# ESP32_MCU.net
KiCad netlist of a schematic drawn in Altium Designer
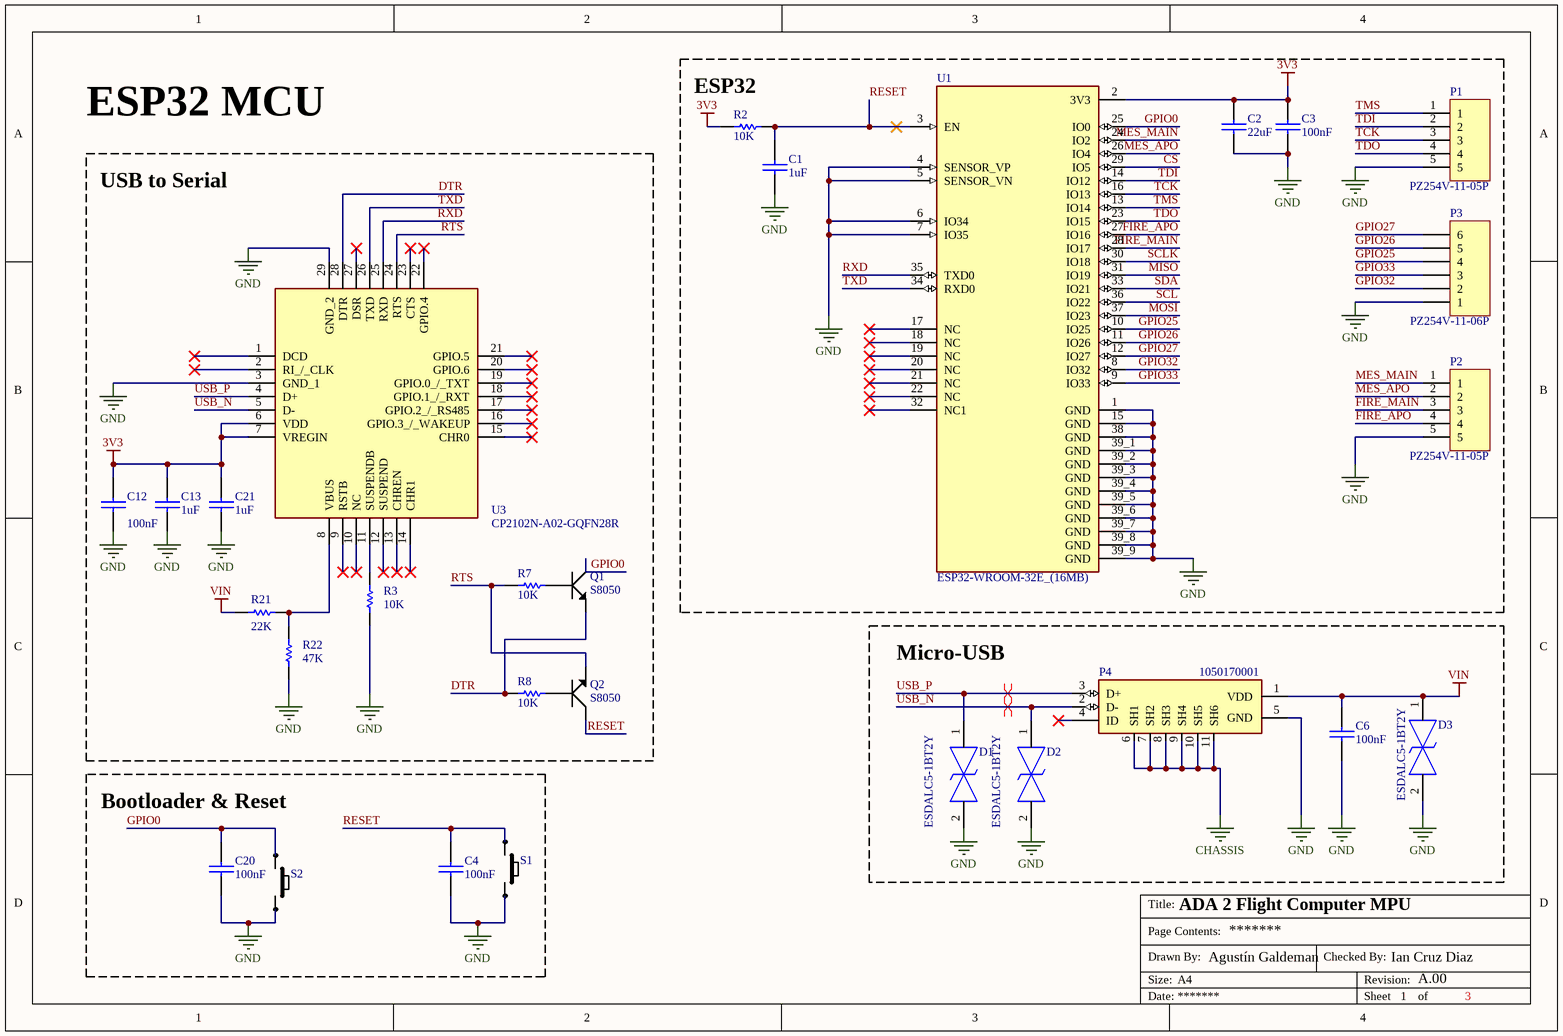
[diagram p0: ESP32 MCU.SchDoc]

(export (version "E")
  (design (tool "Eeschema 10.0.6"))
  (components
    (comp (ref "C1")
      (value "1uF")
      (footprint "CAPSMD0805")
      (description "Capacitor SMD 4.7nF")
      (fields
        (field (name "MANUFACTURER") "FH (Guangdong Fenghua Advanced Tech)")
        (field (name "MANUFACTURER PART NUMBER") "0805F105Z250NT")
      )
      (libsource (lib "ESP32 Platform") (part "CAP"))
    )
    (comp (ref "C2")
      (value "22uF")
      (footprint "CAPSMD0805")
      (description "Capacitor SMD 4.7nF")
      (fields
        (field (name "MANUFACTURER") "Samsung Electro-Mechanics")
        (field (name "MANUFACTURER PART NUMBER") "CL21A226KPCLRNC")
      )
      (libsource (lib "ESP32 Platform") (part "CAP"))
    )
    (comp (ref "C3")
      (value "100nF")
      (footprint "CAPSMD0805")
      (description "Capacitor SMD 4.7nF")
      (fields
        (field (name "MANUFACTURER") "FH (Guangdong Fenghua Advanced Tech)")
        (field (name "MANUFACTURER PART NUMBER") "0805B104M500NT")
      )
      (libsource (lib "ESP32 Platform") (part "CAP"))
    )
    (comp (ref "C4")
      (value "100nF")
      (footprint "CAPSMD0805")
      (description "Capacitor SMD 4.7nF")
      (fields
        (field (name "MANUFACTURER") "FH (Guangdong Fenghua Advanced Tech)")
        (field (name "MANUFACTURER PART NUMBER") "0805B104M500NT")
      )
      (libsource (lib "ESP32 Platform") (part "CAP"))
    )
    (comp (ref "C6")
      (value "100nF")
      (footprint "CAPSMD0805")
      (description "Capacitor SMD 4.7nF")
      (fields
        (field (name "MANUFACTURER") "FH (Guangdong Fenghua Advanced Tech)")
        (field (name "MANUFACTURER PART NUMBER") "0805B104M500NT")
      )
      (libsource (lib "ESP32 Platform") (part "CAP"))
    )
    (comp (ref "C12")
      (value "100nF")
      (footprint "CAPSMD0805")
      (description "Capacitor SMD 4.7nF")
      (fields
        (field (name "MANUFACTURER") "FH (Guangdong Fenghua Advanced Tech)")
        (field (name "MANUFACTURER PART NUMBER") "0805B104M500NT")
      )
      (libsource (lib "ESP32 Platform") (part "CAP"))
    )
    (comp (ref "C13")
      (value "1uF")
      (footprint "CAPSMD0805")
      (description "Capacitor SMD 4.7nF")
      (fields
        (field (name "MANUFACTURER") "FH (Guangdong Fenghua Advanced Tech)")
        (field (name "MANUFACTURER PART NUMBER") "0805F105Z250NT")
      )
      (libsource (lib "ESP32 Platform") (part "CAP"))
    )
    (comp (ref "C20")
      (value "100nF")
      (footprint "CAPSMD0805")
      (description "Capacitor SMD 4.7nF")
      (fields
        (field (name "MANUFACTURER") "FH (Guangdong Fenghua Advanced Tech)")
        (field (name "MANUFACTURER PART NUMBER") "0805B104M500NT")
      )
      (libsource (lib "ESP32 Platform") (part "CAP"))
    )
    (comp (ref "C21")
      (value "1uF")
      (footprint "CAPSMD0805")
      (description "Capacitor SMD 4.7nF")
      (fields
        (field (name "MANUFACTURER") "FH (Guangdong Fenghua Advanced Tech)")
        (field (name "MANUFACTURER PART NUMBER") "0805F105Z250NT")
      )
      (libsource (lib "ESP32 Platform") (part "CAP"))
    )
    (comp (ref "D1")
      (value "~")
      (footprint "ESDALC51BT2")
      (description "ESD Suppressors / TVS Diodes Single Line Transil Vbr 5V min 26pF 0")
      (fields
        (field (name "MANUFACTURER") "STMicroelectronics")
        (field (name "MANUFACTURER PART NUMBER") "ESDALC5-1BT2Y")
      )
      (libsource (lib "ESP32 Platform") (part "ESDALC5-1BT2"))
    )
    (comp (ref "D2")
      (value "~")
      (footprint "ESDALC51BT2")
      (description "ESD Suppressors / TVS Diodes Single Line Transil Vbr 5V min 26pF 0")
      (fields
        (field (name "MANUFACTURER") "STMicroelectronics")
        (field (name "MANUFACTURER PART NUMBER") "ESDALC5-1BT2Y")
      )
      (libsource (lib "ESP32 Platform") (part "ESDALC5-1BT2"))
    )
    (comp (ref "D3")
      (value "~")
      (footprint "ESDALC51BT2")
      (description "ESD Suppressors / TVS Diodes Single Line Transil Vbr 5V min 26pF 0")
      (fields
        (field (name "MANUFACTURER") "STMicroelectronics")
        (field (name "MANUFACTURER PART NUMBER") "ESDALC5-1BT2Y")
      )
      (libsource (lib "ESP32 Platform") (part "ESDALC5-1BT2"))
    )
    (comp (ref "P1")
      (value "HEADER-5P-SR")
      (footprint "PZ254V-11-05P")
      (fields (field (name "MANUFACTURER") "XFCN") (field (name "MANUFACTURER PART NUMBER") "PZ254V-11-05P"))
      (libsource (lib "ESP32 Platform") (part "HEADER-5P-SR"))
    )
    (comp (ref "P2")
      (value "HEADER-5P-SR")
      (footprint "PZ254V-11-05P")
      (fields (field (name "MANUFACTURER") "XFCN") (field (name "MANUFACTURER PART NUMBER") "PZ254V-11-05P"))
      (libsource (lib "ESP32 Platform") (part "HEADER-5P-SR"))
    )
    (comp (ref "P3")
      (value "~")
      (footprint "HDR1X6")
      (description "Header, 6-Pin")
      (fields (field (name "MANUFACTURER") "XFCN") (field (name "MANUFACTURER PART NUMBER") "PZ254V-11-06P"))
      (libsource (lib "Miscellaneous Connectors") (part "Header 6"))
    )
    (comp (ref "P4")
      (value "~")
      (footprint "Micro-B Molex 1051640001")
      (description "USB - micro B USB 2.0 Receptacle Connector 5 Position Surface Mount, Right Angle; Through Hole")
      (fields (field (name "MANUFACTURER") "MOLEX") (field (name "MANUFACTURER PART NUMBER") "1050170001"))
      (libsource (lib "ESP32 Platform") (part "Micro-B Molex 1051640001"))
    )
    (comp (ref "Q1")
      (value "S8050")
      (footprint "SOT-23-3")
      (description "25V 300mW 500mA SOT-23  Bipolar Transistors - BJT ROHS")
      (fields (field (name "MANUFACTURER") "JSMSEMI") (field (name "MANUFACTURER PART NUMBER") "S8050"))
      (libsource (lib "ESP32 Platform") (part "S8050"))
    )
    (comp (ref "Q2")
      (value "S8050")
      (footprint "SOT-23-3")
      (description "25V 300mW 500mA SOT-23  Bipolar Transistors - BJT ROHS")
      (fields (field (name "MANUFACTURER") "JSMSEMI") (field (name "MANUFACTURER PART NUMBER") "S8050"))
      (libsource (lib "ESP32 Platform") (part "S8050"))
    )
    (comp (ref "R2")
      (value "10K")
      (footprint "0805")
      (description "Resistencia SMD 470ohms")
      (fields
        (field (name "MANUFACTURER") "Viking Tech")
        (field (name "MANUFACTURER PART NUMBER") "ARG05BTC1002")
      )
      (libsource (lib "ESP32 Platform") (part "RES"))
    )
    (comp (ref "R3")
      (value "10K")
      (footprint "0805")
      (description "Resistencia SMD 470ohms")
      (fields
        (field (name "MANUFACTURER") "Viking Tech")
        (field (name "MANUFACTURER PART NUMBER") "ARG05BTC1002")
      )
      (libsource (lib "ESP32 Platform") (part "RES"))
    )
    (comp (ref "R7")
      (value "10K")
      (footprint "0805")
      (description "Resistencia SMD 470ohms")
      (fields
        (field (name "MANUFACTURER") "Viking Tech")
        (field (name "MANUFACTURER PART NUMBER") "ARG05BTC1002")
      )
      (libsource (lib "ESP32 Platform") (part "RES"))
    )
    (comp (ref "R8")
      (value "10K")
      (footprint "0805")
      (description "Resistencia SMD 470ohms")
      (fields
        (field (name "MANUFACTURER") "Viking Tech")
        (field (name "MANUFACTURER PART NUMBER") "ARG05BTC1002")
      )
      (libsource (lib "ESP32 Platform") (part "RES"))
    )
    (comp (ref "R21")
      (value "22K")
      (footprint "0805")
      (description "Resistencia SMD 470ohms")
      (fields
        (field (name "MANUFACTURER") "KOA Speer Elec")
        (field (name "MANUFACTURER PART NUMBER") "RN73H2ATTD2202B25")
      )
      (libsource (lib "ESP32 Platform") (part "RES"))
    )
    (comp (ref "R22")
      (value "47K")
      (footprint "0805")
      (description "Resistencia SMD 470ohms")
      (fields
        (field (name "MANUFACTURER") "Sunway")
        (field (name "MANUFACTURER PART NUMBER") "SC0805J4702F4ANRH")
      )
      (libsource (lib "ESP32 Platform") (part "RES"))
    )
    (comp (ref "S1")
      (value "RESET")
      (footprint "PUSHBUTTON_2")
      (description "SWITCH TACTILE SPST-NO 0.05A 12V")
      (fields
        (field (name "MANUFACTURER") "C&K")
        (field (name "MANUFACTURER PART NUMBER") "PTS645SM43SMTR92LFS")
      )
      (libsource (lib "Library") (part "PUSHBUTTON_2"))
    )
    (comp (ref "S2")
      (value "BOOT")
      (footprint "PUSHBUTTON_2")
      (description "SWITCH TACTILE SPST-NO 0.05A 12V")
      (fields
        (field (name "MANUFACTURER") "C&K")
        (field (name "MANUFACTURER PART NUMBER") "PTS645SM43SMTR92LFS")
      )
      (libsource (lib "Library") (part "PUSHBUTTON_2"))
    )
    (comp (ref "U1")
      (value "ESP32-WROOM-32E_(16MB)")
      (footprint "XCVR_ESP32-WROOM-32E_(16MB)")
      (fields
        (field (name "MANUFACTURER") "Espressif Systems")
        (field (name "MANUFACTURER PART NUMBER") "ESP32-WROOM-32E-N16")
      )
      (libsource (lib "ESP32 Platform") (part "ESP32-WROOM-32E_(16MB)"))
    )
    (comp (ref "U3")
      (value "~")
      (footprint "CP2102N")
      (description "USB Interface IC USB to UART bridge - QFN28")
      (fields
        (field (name "MANUFACTURER") "SILICON LABS")
        (field (name "MANUFACTURER PART NUMBER") "CP2102N-A02-GQFN28R")
      )
      (libsource (lib "ESP32 Platform") (part "CP2102N-A02-GQFN28R"))
    )
  )
  (nets
    (net (code "1") (name "/CS") (class "Default")
      (node (ref "U1") (pin "29") (pinfunction "IO5_29") (pintype "bidirectional"))
    )
    (net (code "2") (name "/DTR") (class "Default")
      (node (ref "Q1") (pin "2") (pinfunction "2_2") (pintype "passive"))
      (node (ref "R8") (pin "1") (pinfunction "1_1") (pintype "passive"))
      (node (ref "U3") (pin "28") (pinfunction "DTR_28") (pintype "passive"))
    )
    (net (code "3") (name "/FIRE_APO") (class "Default")
      (node (ref "P2") (pin "4") (pinfunction "4_4") (pintype "passive"))
      (node (ref "U1") (pin "27") (pinfunction "IO16_27") (pintype "bidirectional"))
    )
    (net (code "4") (name "/FIRE_MAIN") (class "Default")
      (node (ref "P2") (pin "3") (pinfunction "3_3") (pintype "passive"))
      (node (ref "U1") (pin "28") (pinfunction "IO17_28") (pintype "bidirectional"))
    )
    (net (code "5") (name "/GPIO0") (class "Default")
      (node (ref "C20") (pin "2") (pinfunction "2_2") (pintype "passive"))
      (node (ref "Q1") (pin "3") (pinfunction "3_3") (pintype "passive"))
      (node (ref "S2") (pin "1") (pinfunction "1_1") (pintype "passive"))
      (node (ref "U1") (pin "25") (pinfunction "IO0_25") (pintype "bidirectional"))
    )
    (net (code "6") (name "/GPIO25") (class "Default")
      (node (ref "P3") (pin "4") (pinfunction "4_4") (pintype "passive"))
      (node (ref "U1") (pin "10") (pinfunction "IO25_10") (pintype "bidirectional"))
    )
    (net (code "7") (name "/GPIO26") (class "Default")
      (node (ref "P3") (pin "5") (pinfunction "5_5") (pintype "passive"))
      (node (ref "U1") (pin "11") (pinfunction "IO26_11") (pintype "bidirectional"))
    )
    (net (code "8") (name "/GPIO27") (class "Default")
      (node (ref "P3") (pin "6") (pinfunction "6_6") (pintype "passive"))
      (node (ref "U1") (pin "12") (pinfunction "IO27_12") (pintype "bidirectional"))
    )
    (net (code "9") (name "/GPIO32") (class "Default")
      (node (ref "P3") (pin "2") (pinfunction "2_2") (pintype "passive"))
      (node (ref "U1") (pin "8") (pinfunction "IO32_8") (pintype "bidirectional"))
    )
    (net (code "10") (name "/GPIO33") (class "Default")
      (node (ref "P3") (pin "3") (pinfunction "3_3") (pintype "passive"))
      (node (ref "U1") (pin "9") (pinfunction "IO33_9") (pintype "bidirectional"))
    )
    (net (code "11") (name "/MES_APO") (class "Default")
      (node (ref "P2") (pin "2") (pinfunction "2_2") (pintype "passive"))
      (node (ref "U1") (pin "26") (pinfunction "IO4_26") (pintype "bidirectional"))
    )
    (net (code "12") (name "/MES_MAIN") (class "Default")
      (node (ref "P2") (pin "1") (pinfunction "1_1") (pintype "passive"))
      (node (ref "U1") (pin "24") (pinfunction "IO2_24") (pintype "bidirectional"))
    )
    (net (code "13") (name "/MISO") (class "Default")
      (node (ref "U1") (pin "31") (pinfunction "IO19_31") (pintype "bidirectional"))
    )
    (net (code "14") (name "/MOSI") (class "Default")
      (node (ref "U1") (pin "37") (pinfunction "IO23_37") (pintype "bidirectional"))
    )
    (net (code "15") (name "/RESET") (class "Default")
      (node (ref "C1") (pin "1") (pinfunction "1_1") (pintype "passive"))
      (node (ref "C4") (pin "2") (pinfunction "2_2") (pintype "passive"))
      (node (ref "Q2") (pin "3") (pinfunction "3_3") (pintype "passive"))
      (node (ref "R2") (pin "2") (pinfunction "2_2") (pintype "passive"))
      (node (ref "S1") (pin "1") (pinfunction "1_1") (pintype "passive"))
      (node (ref "U1") (pin "3") (pinfunction "EN_3") (pintype "input"))
    )
    (net (code "16") (name "/RTS") (class "Default")
      (node (ref "Q2") (pin "2") (pinfunction "2_2") (pintype "passive"))
      (node (ref "R7") (pin "1") (pinfunction "1_1") (pintype "passive"))
      (node (ref "U3") (pin "24") (pinfunction "RTS_24") (pintype "passive"))
    )
    (net (code "17") (name "/RXD") (class "Default")
      (node (ref "U1") (pin "35") (pinfunction "TXD0_35") (pintype "bidirectional"))
      (node (ref "U3") (pin "25") (pinfunction "RXD_25") (pintype "passive"))
    )
    (net (code "18") (name "/SCL") (class "Default")
      (node (ref "U1") (pin "36") (pinfunction "IO22_36") (pintype "bidirectional"))
    )
    (net (code "19") (name "/SCLK") (class "Default")
      (node (ref "U1") (pin "30") (pinfunction "IO18_30") (pintype "bidirectional"))
    )
    (net (code "20") (name "/SDA") (class "Default")
      (node (ref "U1") (pin "33") (pinfunction "IO21_33") (pintype "bidirectional"))
    )
    (net (code "21") (name "/TCK") (class "Default")
      (node (ref "P1") (pin "3") (pinfunction "3_3") (pintype "passive"))
      (node (ref "U1") (pin "16") (pinfunction "IO13_16") (pintype "bidirectional"))
    )
    (net (code "22") (name "/TDI") (class "Default")
      (node (ref "P1") (pin "2") (pinfunction "2_2") (pintype "passive"))
      (node (ref "U1") (pin "14") (pinfunction "IO12_14") (pintype "bidirectional"))
    )
    (net (code "23") (name "/TDO") (class "Default")
      (node (ref "P1") (pin "4") (pinfunction "4_4") (pintype "passive"))
      (node (ref "U1") (pin "23") (pinfunction "IO15_23") (pintype "bidirectional"))
    )
    (net (code "24") (name "/TMS") (class "Default")
      (node (ref "P1") (pin "1") (pinfunction "1_1") (pintype "passive"))
      (node (ref "U1") (pin "13") (pinfunction "IO14_13") (pintype "bidirectional"))
    )
    (net (code "25") (name "/TXD") (class "Default")
      (node (ref "U1") (pin "34") (pinfunction "RXD0_34") (pintype "bidirectional"))
      (node (ref "U3") (pin "26") (pinfunction "TXD_26") (pintype "passive"))
    )
    (net (code "26") (name "/USB_N") (class "Default")
      (node (ref "D2") (pin "1") (pinfunction "1_1") (pintype "passive"))
      (node (ref "P4") (pin "2") (pinfunction "D-_2") (pintype "bidirectional"))
      (node (ref "U3") (pin "5") (pinfunction "D-_5") (pintype "passive"))
    )
    (net (code "27") (name "/USB_P") (class "Default")
      (node (ref "D1") (pin "1") (pinfunction "1_1") (pintype "passive"))
      (node (ref "P4") (pin "3") (pinfunction "D+_3") (pintype "bidirectional"))
      (node (ref "U3") (pin "4") (pinfunction "D+_4") (pintype "passive"))
    )
    (net (code "28") (name "3V3") (class "Default")
      (node (ref "C12") (pin "2") (pinfunction "2_2") (pintype "passive"))
      (node (ref "C13") (pin "1") (pinfunction "1_1") (pintype "passive"))
      (node (ref "C2") (pin "1") (pinfunction "1_1") (pintype "passive"))
      (node (ref "C21") (pin "1") (pinfunction "1_1") (pintype "passive"))
      (node (ref "C3") (pin "2") (pinfunction "2_2") (pintype "passive"))
      (node (ref "R2") (pin "1") (pinfunction "1_1") (pintype "passive"))
      (node (ref "U1") (pin "2") (pinfunction "3V3_2") (pintype "power_in"))
      (node (ref "U3") (pin "6") (pinfunction "VDD_6") (pintype "passive"))
      (node (ref "U3") (pin "7") (pinfunction "VREGIN_7") (pintype "passive"))
    )
    (net (code "29") (name "CHASSIS") (class "Default")
      (node (ref "P4") (pin "10") (pinfunction "SH5_10") (pintype "passive"))
      (node (ref "P4") (pin "11") (pinfunction "SH6_11") (pintype "passive"))
      (node (ref "P4") (pin "6") (pinfunction "SH1_6") (pintype "passive"))
      (node (ref "P4") (pin "7") (pinfunction "SH2_7") (pintype "passive"))
      (node (ref "P4") (pin "8") (pinfunction "SH3_8") (pintype "passive"))
      (node (ref "P4") (pin "9") (pinfunction "SH4_9") (pintype "passive"))
    )
    (net (code "30") (name "GND") (class "Default")
      (node (ref "C1") (pin "2") (pinfunction "2_2") (pintype "passive"))
      (node (ref "C12") (pin "1") (pinfunction "1_1") (pintype "passive"))
      (node (ref "C13") (pin "2") (pinfunction "2_2") (pintype "passive"))
      (node (ref "C2") (pin "2") (pinfunction "2_2") (pintype "passive"))
      (node (ref "C20") (pin "1") (pinfunction "1_1") (pintype "passive"))
      (node (ref "C21") (pin "2") (pinfunction "2_2") (pintype "passive"))
      (node (ref "C3") (pin "1") (pinfunction "1_1") (pintype "passive"))
      (node (ref "C4") (pin "1") (pinfunction "1_1") (pintype "passive"))
      (node (ref "C6") (pin "1") (pinfunction "1_1") (pintype "passive"))
      (node (ref "D1") (pin "2") (pinfunction "2_2") (pintype "passive"))
      (node (ref "D2") (pin "2") (pinfunction "2_2") (pintype "passive"))
      (node (ref "D3") (pin "2") (pinfunction "2_2") (pintype "passive"))
      (node (ref "P1") (pin "5") (pinfunction "5_5") (pintype "passive"))
      (node (ref "P2") (pin "5") (pinfunction "5_5") (pintype "passive"))
      (node (ref "P3") (pin "1") (pinfunction "1_1") (pintype "passive"))
      (node (ref "P4") (pin "5") (pinfunction "GND_5") (pintype "power_in"))
      (node (ref "R22") (pin "1") (pinfunction "1_1") (pintype "passive"))
      (node (ref "R3") (pin "2") (pinfunction "2_2") (pintype "passive"))
      (node (ref "S1") (pin "2") (pinfunction "2_2") (pintype "passive"))
      (node (ref "S2") (pin "2") (pinfunction "2_2") (pintype "passive"))
      (node (ref "U1") (pin "1") (pinfunction "GND_1") (pintype "power_in"))
      (node (ref "U1") (pin "15") (pinfunction "GND_15") (pintype "power_in"))
      (node (ref "U1") (pin "38") (pinfunction "GND_38") (pintype "power_in"))
      (node (ref "U1") (pin "39_1") (pinfunction "GND_39_1") (pintype "power_in"))
      (node (ref "U1") (pin "39_2") (pinfunction "GND_39_2") (pintype "power_in"))
      (node (ref "U1") (pin "39_3") (pinfunction "GND_39_3") (pintype "power_in"))
      (node (ref "U1") (pin "39_4") (pinfunction "GND_39_4") (pintype "power_in"))
      (node (ref "U1") (pin "39_5") (pinfunction "GND_39_5") (pintype "power_in"))
      (node (ref "U1") (pin "39_6") (pinfunction "GND_39_6") (pintype "power_in"))
      (node (ref "U1") (pin "39_7") (pinfunction "GND_39_7") (pintype "power_in"))
      (node (ref "U1") (pin "39_8") (pinfunction "GND_39_8") (pintype "power_in"))
      (node (ref "U1") (pin "39_9") (pinfunction "GND_39_9") (pintype "power_in"))
      (node (ref "U1") (pin "4") (pinfunction "SENSOR_VP_4") (pintype "input"))
      (node (ref "U1") (pin "5") (pinfunction "SENSOR_VN_5") (pintype "input"))
      (node (ref "U1") (pin "6") (pinfunction "IO34_6") (pintype "input"))
      (node (ref "U1") (pin "7") (pinfunction "IO35_7") (pintype "input"))
      (node (ref "U3") (pin "29") (pinfunction "GND_2_29") (pintype "passive"))
      (node (ref "U3") (pin "3") (pinfunction "GND_1_3") (pintype "passive"))
    )
    (net (code "31") (name "Net-(Q1-Pad1)") (class "Default")
      (node (ref "Q1") (pin "1") (pinfunction "1_1") (pintype "passive"))
      (node (ref "R7") (pin "2") (pinfunction "2_2") (pintype "passive"))
    )
    (net (code "32") (name "Net-(Q2-Pad1)") (class "Default")
      (node (ref "Q2") (pin "1") (pinfunction "1_1") (pintype "passive"))
      (node (ref "R8") (pin "2") (pinfunction "2_2") (pintype "passive"))
    )
    (net (code "33") (name "Net-(U3-SUSPENDB)") (class "Default")
      (node (ref "R3") (pin "1") (pinfunction "1_1") (pintype "passive"))
      (node (ref "U3") (pin "11") (pinfunction "SUSPENDB_11") (pintype "passive"))
    )
    (net (code "34") (name "Net-(U3-VBUS)") (class "Default")
      (node (ref "R21") (pin "2") (pinfunction "2_2") (pintype "passive"))
      (node (ref "R22") (pin "2") (pinfunction "2_2") (pintype "passive"))
      (node (ref "U3") (pin "8") (pinfunction "VBUS_8") (pintype "passive"))
    )
    (net (code "35") (name "VIN") (class "Default")
      (node (ref "C6") (pin "2") (pinfunction "2_2") (pintype "passive"))
      (node (ref "D3") (pin "1") (pinfunction "1_1") (pintype "passive"))
      (node (ref "P4") (pin "1") (pinfunction "VDD_1") (pintype "power_in"))
      (node (ref "R21") (pin "1") (pinfunction "1_1") (pintype "passive"))
    )
    (net (code "36") (name "unconnected-(P4-ID-Pad4)") (class "Default")
      (node (ref "P4") (pin "4") (pinfunction "ID_4") (pintype "passive+no_connect"))
    )
    (net (code "37") (name "unconnected-(U1-NC-Pad17)") (class "Default")
      (node (ref "U1") (pin "17") (pinfunction "NC_17") (pintype "passive+no_connect"))
    )
    (net (code "38") (name "unconnected-(U1-NC-Pad18)") (class "Default")
      (node (ref "U1") (pin "18") (pinfunction "NC_18") (pintype "passive+no_connect"))
    )
    (net (code "39") (name "unconnected-(U1-NC-Pad19)") (class "Default")
      (node (ref "U1") (pin "19") (pinfunction "NC_19") (pintype "passive+no_connect"))
    )
    (net (code "40") (name "unconnected-(U1-NC-Pad20)") (class "Default")
      (node (ref "U1") (pin "20") (pinfunction "NC_20") (pintype "passive+no_connect"))
    )
    (net (code "41") (name "unconnected-(U1-NC-Pad21)") (class "Default")
      (node (ref "U1") (pin "21") (pinfunction "NC_21") (pintype "passive+no_connect"))
    )
    (net (code "42") (name "unconnected-(U1-NC-Pad22)") (class "Default")
      (node (ref "U1") (pin "22") (pinfunction "NC_22") (pintype "passive+no_connect"))
    )
    (net (code "43") (name "unconnected-(U1-NC1-Pad32)") (class "Default")
      (node (ref "U1") (pin "32") (pinfunction "NC1_32") (pintype "passive+no_connect"))
    )
    (net (code "44") (name "unconnected-(U3-CHR0-Pad15)") (class "Default")
      (node (ref "U3") (pin "15") (pinfunction "CHR0_15") (pintype "passive+no_connect"))
    )
    (net (code "45") (name "unconnected-(U3-CHR1-Pad14)") (class "Default")
      (node (ref "U3") (pin "14") (pinfunction "CHR1_14") (pintype "passive+no_connect"))
    )
    (net (code "46") (name "unconnected-(U3-CHREN-Pad13)") (class "Default")
      (node (ref "U3") (pin "13") (pinfunction "CHREN_13") (pintype "passive+no_connect"))
    )
    (net (code "47") (name "unconnected-(U3-CTS-Pad23)") (class "Default")
      (node (ref "U3") (pin "23") (pinfunction "CTS_23") (pintype "passive+no_connect"))
    )
    (net (code "48") (name "unconnected-(U3-DCD-Pad1)") (class "Default")
      (node (ref "U3") (pin "1") (pinfunction "DCD_1") (pintype "passive+no_connect"))
    )
    (net (code "49") (name "unconnected-(U3-DSR-Pad27)") (class "Default")
      (node (ref "U3") (pin "27") (pinfunction "DSR_27") (pintype "passive+no_connect"))
    )
    (net (code "50") (name "unconnected-(U3-GPIO.0_{slash}_TXT-Pad19)") (class "Default")
      (node (ref "U3") (pin "19") (pinfunction "GPIO.0_/_TXT_19") (pintype "passive+no_connect"))
    )
    (net (code "51") (name "unconnected-(U3-GPIO.1_{slash}_RXT-Pad18)") (class "Default")
      (node (ref "U3") (pin "18") (pinfunction "GPIO.1_/_RXT_18") (pintype "passive+no_connect"))
    )
    (net (code "52") (name "unconnected-(U3-GPIO.2_{slash}_RS485-Pad17)") (class "Default")
      (node (ref "U3") (pin "17") (pinfunction "GPIO.2_/_RS485_17") (pintype "passive+no_connect"))
    )
    (net (code "53") (name "unconnected-(U3-GPIO.3_{slash}_WAKEUP-Pad16)") (class "Default")
      (node (ref "U3") (pin "16") (pinfunction "GPIO.3_/_WAKEUP_16") (pintype "passive+no_connect"))
    )
    (net (code "54") (name "unconnected-(U3-GPIO.4-Pad22)") (class "Default")
      (node (ref "U3") (pin "22") (pinfunction "GPIO.4_22") (pintype "passive+no_connect"))
    )
    (net (code "55") (name "unconnected-(U3-GPIO.5-Pad21)") (class "Default")
      (node (ref "U3") (pin "21") (pinfunction "GPIO.5_21") (pintype "passive+no_connect"))
    )
    (net (code "56") (name "unconnected-(U3-GPIO.6-Pad20)") (class "Default")
      (node (ref "U3") (pin "20") (pinfunction "GPIO.6_20") (pintype "passive+no_connect"))
    )
    (net (code "57") (name "unconnected-(U3-NC-Pad10)") (class "Default")
      (node (ref "U3") (pin "10") (pinfunction "NC_10") (pintype "passive+no_connect"))
    )
    (net (code "58") (name "unconnected-(U3-RI_{slash}_CLK-Pad2)") (class "Default")
      (node (ref "U3") (pin "2") (pinfunction "RI_/_CLK_2") (pintype "passive+no_connect"))
    )
    (net (code "59") (name "unconnected-(U3-RSTB-Pad9)") (class "Default")
      (node (ref "U3") (pin "9") (pinfunction "RSTB_9") (pintype "passive+no_connect"))
    )
    (net (code "60") (name "unconnected-(U3-SUSPEND-Pad12)") (class "Default")
      (node (ref "U3") (pin "12") (pinfunction "SUSPEND_12") (pintype "passive+no_connect"))
    )
  )
)
